# SDI12_Interface.net
KiCad netlist of a schematic drawn in EAGLE
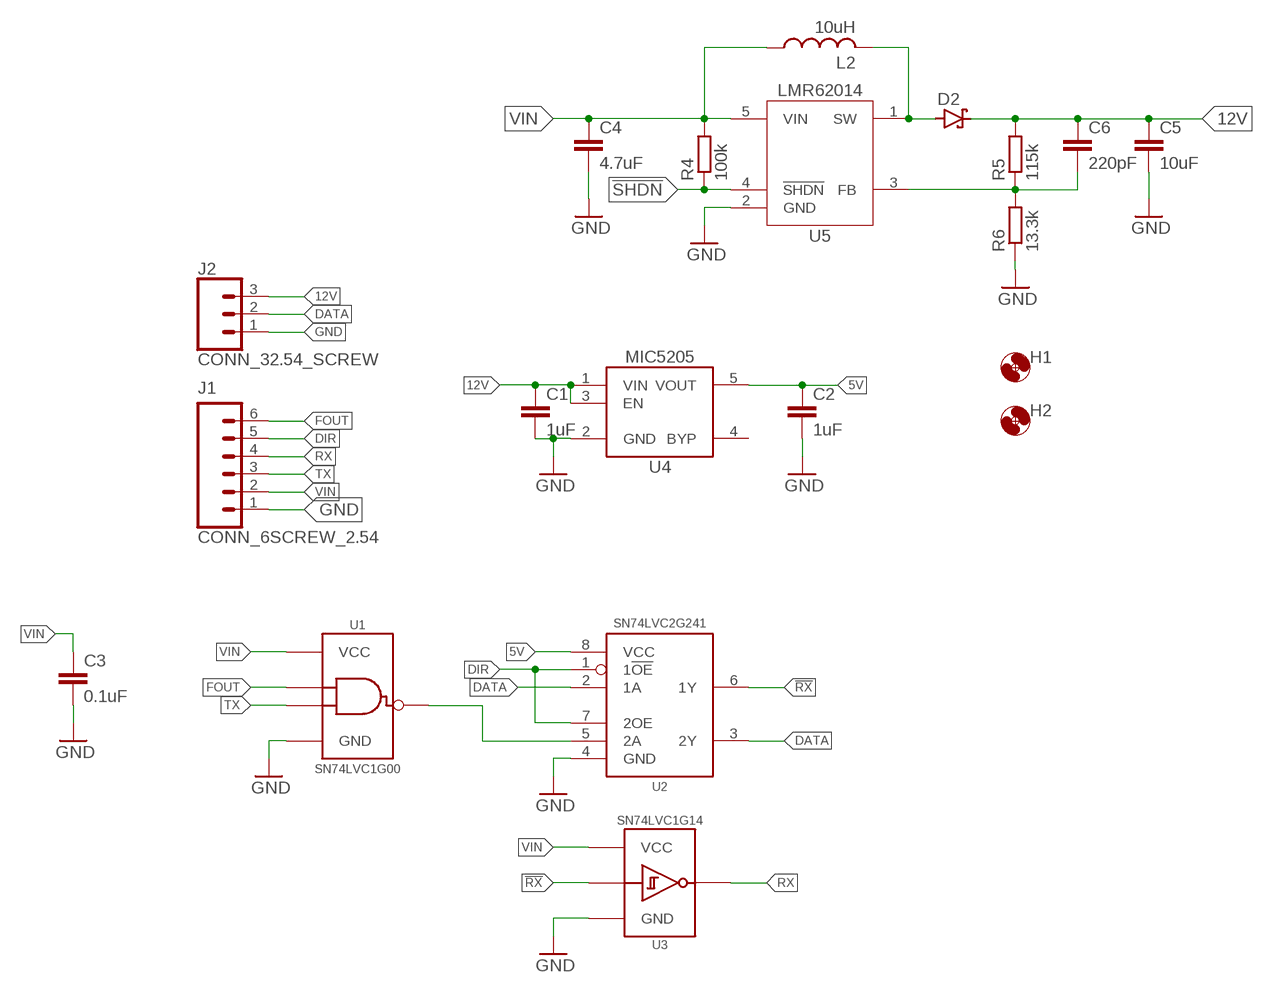
[diagram p0: schematic, sheet 1]

(export (version "E")
  (design (tool "Eeschema 10.0.6"))
  (components
    (comp (ref "C1")
      (value "1uF")
      (footprint "eagle-import:C0603")
      (fields (field (name "MF") "Yaiyo Yuden") (field (name "MPN") "EMK107BJ105KA-T"))
      (libsource (lib "eagle-import") (part "C-EUC06031UF"))
    )
    (comp (ref "C2")
      (value "1uF")
      (footprint "eagle-import:C0603")
      (fields (field (name "MF") "Yaiyo Yuden") (field (name "MPN") "EMK107BJ105KA-T"))
      (libsource (lib "eagle-import") (part "C-EUC06031UF"))
    )
    (comp (ref "C3")
      (value "0.1uF")
      (footprint "eagle-import:C0603")
      (fields (field (name "MF") "Murata") (field (name "MPN") "GCM188R71E104KA57D"))
      (libsource (lib "eagle-import") (part "C-EUC06030.1UF"))
    )
    (comp (ref "C4")
      (value "4.7uF")
      (footprint "eagle-import:C0805")
      (fields (field (name "MF") "Kemet") (field (name "MPN") "C0805C475K4RACTU"))
      (libsource (lib "eagle-import") (part "C-EUC08054.7UF"))
    )
    (comp (ref "C5")
      (value "10uF")
      (footprint "eagle-import:C0805")
      (fields
        (field (name "MF") "Murata")
        (field (name "MPN") "GRM21BR61C106KE15K")
        (field (name "DIGIKEY") "587-2985-1-ND")
        (field (name "MF_1") "Taiyo Yuden")
        (field (name "MPN_1") "TMK212BBJ106KG-T")
      )
      (libsource (lib "eagle-import") (part "C-EUC080510UF"))
    )
    (comp (ref "C6")
      (value "220pF")
      (footprint "eagle-import:C0603")
      (fields (field (name "MF") "Kemet") (field (name "MPN") "C0603C221J5GACTU"))
      (libsource (lib "eagle-import") (part "C-EUC0603220PF"))
    )
    (comp (ref "D2")
      (value "DIODE_SCHOTTKYSOD-123")
      (footprint "eagle-import:SOD-123")
      (fields (field (name "MF") "ON Semiconductor") (field (name "MPN") "MBR0520LT1G"))
      (libsource (lib "eagle-import") (part "DIODE_SCHOTTKYSOD-123"))
    )
    (comp (ref "H1")
      (value "MOUNTING_HOLE2_NP")
      (footprint "eagle-import:2_56")
      (fields (field (name "MPN") "DNP"))
      (libsource (lib "eagle-import") (part "MOUNTING_HOLE2_NP"))
    )
    (comp (ref "H2")
      (value "MOUNTING_HOLE2_NP")
      (footprint "eagle-import:2_56")
      (fields (field (name "MPN") "DNP"))
      (libsource (lib "eagle-import") (part "MOUNTING_HOLE2_NP"))
    )
    (comp (ref "J1")
      (value "CONN_6SCREW_2.54")
      (footprint "eagle-import:1X06_SCREW")
      (fields (field (name "MF") "OnShore") (field (name "MPN") "OSTVN06A150"))
      (libsource (lib "eagle-import") (part "CONN_6SCREW_2.54"))
    )
    (comp (ref "J2")
      (value "CONN_32.54_SCREW")
      (footprint "eagle-import:1X03_SCREW")
      (fields (field (name "MF") "On Shore") (field (name "MPN") "OSTVN03A150"))
      (libsource (lib "eagle-import") (part "CONN_32.54_SCREW"))
    )
    (comp (ref "L2")
      (value "10uH")
      (footprint "eagle-import:1008")
      (fields (field (name "MF") "Wurth") (field (name "MPN") "74438323100"))
      (libsource (lib "eagle-import") (part "INDUCTOR1008"))
    )
    (comp (ref "R4")
      (value "100k")
      (footprint "eagle-import:R0603")
      (fields (field (name "MF") "Yageo") (field (name "MPN") "RC0603FR-07100KL"))
      (libsource (lib "eagle-import") (part "R-EU_R0603100K"))
    )
    (comp (ref "R5")
      (value "115k")
      (footprint "eagle-import:R0603")
      (fields (field (name "MF") "Yageo") (field (name "MPN") "RC0603FR-07115KL"))
      (libsource (lib "eagle-import") (part "R-EU_R0603115K"))
    )
    (comp (ref "R6")
      (value "13.3k")
      (footprint "eagle-import:R0603")
      (fields (field (name "MF") "Yageo") (field (name "MPN") "RC0603FR-0713K3L"))
      (libsource (lib "eagle-import") (part "R-EU_R060313.3K"))
    )
    (comp (ref "U1")
      (value "SN74LVC1G00SC70")
      (footprint "eagle-import:DCK_R-PDSO-G5")
      (fields (field (name "DISP") "SN74LVC1G00") (field (name "MPN") "SN74LVC1G00DCKR"))
      (libsource (lib "eagle-import") (part "SN74LVC1G00SC70"))
    )
    (comp (ref "U2")
      (value "SN74LVC2G241DCU")
      (footprint "eagle-import:DCU_(R-PDSO-G8)")
      (fields (field (name "MF") "TI") (field (name "MPN") "SN74LVC2G241DCUT"))
      (libsource (lib "eagle-import") (part "SN74LVC2G241DCU"))
    )
    (comp (ref "U3")
      (value "SN74LVC1G14DCK")
      (footprint "eagle-import:DCK_R-PDSO-G5")
      (fields
        (field (name "DISP") "SN74LVC1G14")
        (field (name "MF") "TI")
        (field (name "MPN") "SN74LVC1G14DCKR")
      )
      (libsource (lib "eagle-import") (part "SN741G14DCKLVC"))
    )
    (comp (ref "U4")
      (value "MIC5205_5V")
      (footprint "eagle-import:SOT23-5")
      (fields (field (name "MF") "Microchip") (field (name "MPN") "MIC5205-5.0YM5-TR"))
      (libsource (lib "eagle-import") (part "MIC5205_5V"))
    )
    (comp (ref "U5")
      (value "LMR62014SOT23")
      (footprint "eagle-import:DBV0005A")
      (fields
        (field (name "DISP") "LMR62014")
        (field (name "MF") "TI")
        (field (name "MPN") "LMR62014XMF/NOPB")
      )
      (libsource (lib "eagle-import") (part "LMR62014SOT23"))
    )
  )
  (nets
    (net (code "1") (name "/BYP") (class "Default")
      (node (ref "U4") (pin "4") (pinfunction "BYP_4") (pintype "power_in"))
    )
    (net (code "2") (name "/~{RX}") (class "Default")
      (node (ref "U2") (pin "6") (pinfunction "1Y_6") (pintype "output"))
      (node (ref "U3") (pin "2") (pinfunction "A_2") (pintype "input"))
    )
    (net (code "3") (name "/~{SHDN}") (class "Default")
      (node (ref "R4") (pin "1") (pinfunction "1_1") (pintype "passive"))
      (node (ref "U5") (pin "4") (pinfunction "~{SHDN}_4") (pintype "input"))
    )
    (net (code "4") (name "5V") (class "Default")
      (node (ref "C2") (pin "1") (pinfunction "1_1") (pintype "passive"))
      (node (ref "U2") (pin "8") (pinfunction "VCC_8") (pintype "power_in"))
      (node (ref "U4") (pin "5") (pinfunction "VOUT_5") (pintype "power_in"))
    )
    (net (code "5") (name "12V") (class "Default")
      (node (ref "C1") (pin "1") (pinfunction "1_1") (pintype "passive"))
      (node (ref "C5") (pin "1") (pinfunction "1_1") (pintype "passive"))
      (node (ref "C6") (pin "1") (pinfunction "1_1") (pintype "passive"))
      (node (ref "D2") (pin "CAT") (pinfunction "C_CAT") (pintype "passive"))
      (node (ref "J2") (pin "3") (pinfunction "3_3") (pintype "passive"))
      (node (ref "R5") (pin "2") (pinfunction "2_2") (pintype "passive"))
      (node (ref "U4") (pin "1") (pinfunction "VIN_1") (pintype "power_in"))
      (node (ref "U4") (pin "3") (pinfunction "EN_3") (pintype "input"))
    )
    (net (code "6") (name "DATA") (class "Default")
      (node (ref "J2") (pin "2") (pinfunction "2_2") (pintype "passive"))
      (node (ref "U2") (pin "2") (pinfunction "1A_2") (pintype "input"))
      (node (ref "U2") (pin "3") (pinfunction "2Y_3") (pintype "output"))
    )
    (net (code "7") (name "DIR") (class "Default")
      (node (ref "J1") (pin "5") (pinfunction "5_5") (pintype "passive"))
      (node (ref "U2") (pin "1") (pinfunction "1~{OE}_1") (pintype "input"))
      (node (ref "U2") (pin "7") (pinfunction "2OE_7") (pintype "input"))
    )
    (net (code "8") (name "FOUT") (class "Default")
      (node (ref "J1") (pin "6") (pinfunction "6_6") (pintype "passive"))
      (node (ref "U1") (pin "1") (pinfunction "A_1") (pintype "input"))
    )
    (net (code "9") (name "GND") (class "Default")
      (node (ref "C1") (pin "2") (pinfunction "2_2") (pintype "passive"))
      (node (ref "C2") (pin "2") (pinfunction "2_2") (pintype "passive"))
      (node (ref "C3") (pin "2") (pinfunction "2_2") (pintype "passive"))
      (node (ref "C4") (pin "2") (pinfunction "2_2") (pintype "passive"))
      (node (ref "C5") (pin "2") (pinfunction "2_2") (pintype "passive"))
      (node (ref "J1") (pin "1") (pinfunction "1_1") (pintype "passive"))
      (node (ref "J2") (pin "1") (pinfunction "1_1") (pintype "passive"))
      (node (ref "R6") (pin "1") (pinfunction "1_1") (pintype "passive"))
      (node (ref "U1") (pin "3") (pinfunction "GND_3") (pintype "power_in"))
      (node (ref "U2") (pin "4") (pinfunction "GND_4") (pintype "power_in"))
      (node (ref "U3") (pin "3") (pinfunction "GND_3") (pintype "power_in"))
      (node (ref "U4") (pin "2") (pinfunction "GND_2") (pintype "power_in"))
      (node (ref "U5") (pin "2") (pinfunction "GND_2") (pintype "power_in"))
    )
    (net (code "10") (name "Net-(D2-A)") (class "Default")
      (node (ref "D2") (pin "ANODE") (pinfunction "A_ANODE") (pintype "passive"))
      (node (ref "L2") (pin "2") (pinfunction "2_2") (pintype "passive"))
      (node (ref "U5") (pin "1") (pinfunction "SW_1") (pintype "power_in"))
    )
    (net (code "11") (name "Net-(U1-Y)") (class "Default")
      (node (ref "U1") (pin "4") (pinfunction "Y_4") (pintype "output"))
      (node (ref "U2") (pin "5") (pinfunction "2A_5") (pintype "input"))
    )
    (net (code "12") (name "Net-(U5-FB)") (class "Default")
      (node (ref "C6") (pin "2") (pinfunction "2_2") (pintype "passive"))
      (node (ref "R5") (pin "1") (pinfunction "1_1") (pintype "passive"))
      (node (ref "R6") (pin "2") (pinfunction "2_2") (pintype "passive"))
      (node (ref "U5") (pin "3") (pinfunction "FB_3") (pintype "input"))
    )
    (net (code "13") (name "RX") (class "Default")
      (node (ref "J1") (pin "4") (pinfunction "4_4") (pintype "passive"))
      (node (ref "U3") (pin "4") (pinfunction "Y_4") (pintype "output"))
    )
    (net (code "14") (name "TX") (class "Default")
      (node (ref "J1") (pin "3") (pinfunction "3_3") (pintype "passive"))
      (node (ref "U1") (pin "2") (pinfunction "B_2") (pintype "input"))
    )
    (net (code "15") (name "VIN") (class "Default")
      (node (ref "C3") (pin "1") (pinfunction "1_1") (pintype "passive"))
      (node (ref "C4") (pin "1") (pinfunction "1_1") (pintype "passive"))
      (node (ref "J1") (pin "2") (pinfunction "2_2") (pintype "passive"))
      (node (ref "L2") (pin "1") (pinfunction "1_1") (pintype "passive"))
      (node (ref "R4") (pin "2") (pinfunction "2_2") (pintype "passive"))
      (node (ref "U1") (pin "5") (pinfunction "VCC_5") (pintype "power_in"))
      (node (ref "U3") (pin "5") (pinfunction "VCC_5") (pintype "power_in"))
      (node (ref "U5") (pin "5") (pinfunction "VIN_5") (pintype "power_in"))
    )
  )
)
